# GND_FAULT.net
KiCad netlist of a schematic drawn in Altium Designer
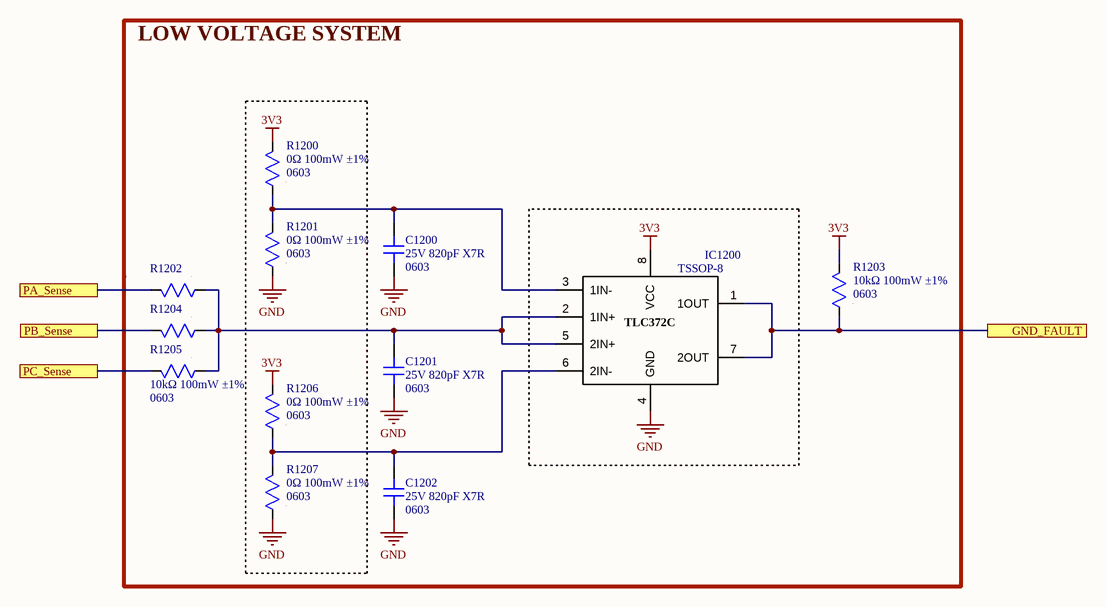
[diagram p0: GND_FAULT.SchDoc]

(export (version "E")
  (design (tool "Eeschema 10.0.6"))
  (components
    (comp (ref "C1200")
      (value "25V 820pF X7R")
      (footprint "CAP SMD 0603")
      (description "Condensadores de cerámica multicapa (MLCC- SMD/SMT) 25V 820pF X7R 0603 1 0% Tol")
      (fields
        (field (name "PACKAGE") "0603")
        (field (name "MPN") "06033C821KAT2A")
        (field (name "MANUFACTURER") "KYOCERA AVX")
      )
      (libsource (lib "eUSR_Database") (part "CAP non polarized"))
    )
    (comp (ref "C1201")
      (value "25V 820pF X7R")
      (footprint "CAP SMD 0603")
      (description "Condensadores de cerámica multicapa (MLCC- SMD/SMT) 25V 820pF X7R 0603 1 0% Tol")
      (fields
        (field (name "PACKAGE") "0603")
        (field (name "MPN") "06033C821KAT2A")
        (field (name "MANUFACTURER") "KYOCERA AVX")
      )
      (libsource (lib "eUSR_Database") (part "CAP non polarized"))
    )
    (comp (ref "C1202")
      (value "25V 820pF X7R")
      (footprint "CAP SMD 0603")
      (description "Condensadores de cerámica multicapa (MLCC- SMD/SMT) 25V 820pF X7R 0603 1 0% Tol")
      (fields
        (field (name "PACKAGE") "0603")
        (field (name "MPN") "06033C821KAT2A")
        (field (name "MANUFACTURER") "KYOCERA AVX")
      )
      (libsource (lib "eUSR_Database") (part "CAP non polarized"))
    )
    (comp (ref "IC1200")
      (value "TLC372C")
      (footprint "TSSOP-8")
      (description "Comparadores analógicos Dual Differential A 595-TLC372CPW A 595- A 595-TLC372CPW")
      (fields
        (field (name "PACKAGE") "TSSOP-8")
        (field (name "MPN") "TLC372CPWR")
        (field (name "MANUFACTURER") "Texas Instruments")
      )
      (libsource (lib "eUSR_Database") (part "TLC372C"))
    )
    (comp (ref "R1200")
      (value "0Ω 100mW ±1%")
      (footprint "RES SMD 0603")
      (description "Resistores de película gruesa - SMD WRIS-RSKS <0.05 Ohms 0.1 W Jumper 0603 AEC-Q200")
      (fields
        (field (name "PACKAGE") "0603")
        (field (name "MPN") "560112116001")
        (field (name "MANUFACTURER") "Wurth Elektronik")
      )
      (libsource (lib "eUSR_Database") (part "RES"))
    )
    (comp (ref "R1201")
      (value "0Ω 100mW ±1%")
      (footprint "RES SMD 0603")
      (description "Resistores de película gruesa - SMD WRIS-RSKS <0.05 Ohms 0.1 W Jumper 0603 AEC-Q200")
      (fields
        (field (name "PACKAGE") "0603")
        (field (name "MPN") "560112116001")
        (field (name "MANUFACTURER") "Wurth Elektronik")
      )
      (libsource (lib "eUSR_Database") (part "RES"))
    )
    (comp (ref "R1202")
      (value "RES")
      (footprint "RES SMD 0603")
      (description "Resistores de película gruesa - SMD WRIS-RSKS 10 kOhms 1 % 0.1 W 0603 AEC-Q200")
      (fields (field (name "MPN") "560112116005") (field (name "MANUFACTURER") "Wurth Elektronik"))
      (libsource (lib "eUSR_Database") (part "RES"))
    )
    (comp (ref "R1203")
      (value "10kΩ 100mW ±1%")
      (footprint "RES SMD 0603")
      (description "Resistores de película gruesa - SMD WRIS-RSKS 10 kOhms 1 % 0.1 W 0603 AEC-Q200")
      (fields
        (field (name "PACKAGE") "0603")
        (field (name "MPN") "560112116005")
        (field (name "MANUFACTURER") "Wurth Elektronik")
      )
      (libsource (lib "eUSR_Database") (part "RES"))
    )
    (comp (ref "R1204")
      (value "RES")
      (footprint "RES SMD 0603")
      (description "Resistores de película gruesa - SMD WRIS-RSKS 10 kOhms 1 % 0.1 W 0603 AEC-Q200")
      (fields (field (name "MPN") "560112116005") (field (name "MANUFACTURER") "Wurth Elektronik"))
      (libsource (lib "eUSR_Database") (part "RES"))
    )
    (comp (ref "R1205")
      (value "10kΩ 100mW ±1%")
      (footprint "RES SMD 0603")
      (description "Resistores de película gruesa - SMD WRIS-RSKS 10 kOhms 1 % 0.1 W 0603 AEC-Q200")
      (fields
        (field (name "PACKAGE") "0603")
        (field (name "MPN") "560112116005")
        (field (name "MANUFACTURER") "Wurth Elektronik")
      )
      (libsource (lib "eUSR_Database") (part "RES"))
    )
    (comp (ref "R1206")
      (value "0Ω 100mW ±1%")
      (footprint "RES SMD 0603")
      (description "Resistores de película gruesa - SMD WRIS-RSKS <0.05 Ohms 0.1 W Jumper 0603 AEC-Q200")
      (fields
        (field (name "PACKAGE") "0603")
        (field (name "MPN") "560112116001")
        (field (name "MANUFACTURER") "Wurth Elektronik")
      )
      (libsource (lib "eUSR_Database") (part "RES"))
    )
    (comp (ref "R1207")
      (value "0Ω 100mW ±1%")
      (footprint "RES SMD 0603")
      (description "Resistores de película gruesa - SMD WRIS-RSKS <0.05 Ohms 0.1 W Jumper 0603 AEC-Q200")
      (fields
        (field (name "PACKAGE") "0603")
        (field (name "MPN") "560112116001")
        (field (name "MANUFACTURER") "Wurth Elektronik")
      )
      (libsource (lib "eUSR_Database") (part "RES"))
    )
  )
  (nets
    (net (code "1") (name "/GND_FAULT") (class "Default")
      (node (ref "IC1200") (pin "1") (pinfunction "1OUT_1") (pintype "passive"))
      (node (ref "IC1200") (pin "7") (pinfunction "2OUT_7") (pintype "passive"))
      (node (ref "R1203") (pin "1") (pinfunction "1_1") (pintype "passive"))
    )
    (net (code "2") (name "/PA_Sense") (class "Default")
      (node (ref "R1202") (pin "2") (pinfunction "2_2") (pintype "passive"))
    )
    (net (code "3") (name "/PB_Sense") (class "Default")
      (node (ref "R1204") (pin "2") (pinfunction "2_2") (pintype "passive"))
    )
    (net (code "4") (name "/PC_Sense") (class "Default")
      (node (ref "R1205") (pin "2") (pinfunction "2_2") (pintype "passive"))
    )
    (net (code "5") (name "3V3") (class "Default")
      (node (ref "IC1200") (pin "8") (pinfunction "VCC_8") (pintype "passive"))
      (node (ref "R1200") (pin "2") (pinfunction "2_2") (pintype "passive"))
      (node (ref "R1203") (pin "2") (pinfunction "2_2") (pintype "passive"))
      (node (ref "R1206") (pin "2") (pinfunction "2_2") (pintype "passive"))
    )
    (net (code "6") (name "GND") (class "Default")
      (node (ref "C1200") (pin "2") (pinfunction "2_2") (pintype "passive"))
      (node (ref "C1201") (pin "2") (pinfunction "2_2") (pintype "passive"))
      (node (ref "C1202") (pin "2") (pinfunction "2_2") (pintype "passive"))
      (node (ref "IC1200") (pin "4") (pinfunction "GND_4") (pintype "passive"))
      (node (ref "R1201") (pin "1") (pinfunction "1_1") (pintype "passive"))
      (node (ref "R1207") (pin "1") (pinfunction "1_1") (pintype "passive"))
    )
    (net (code "7") (name "Net-(IC1200-1IN+)") (class "Default")
      (node (ref "C1201") (pin "1") (pinfunction "1_1") (pintype "passive"))
      (node (ref "IC1200") (pin "2") (pinfunction "1IN+_2") (pintype "passive"))
      (node (ref "IC1200") (pin "5") (pinfunction "2IN+_5") (pintype "passive"))
      (node (ref "R1202") (pin "1") (pinfunction "1_1") (pintype "passive"))
      (node (ref "R1204") (pin "1") (pinfunction "1_1") (pintype "passive"))
      (node (ref "R1205") (pin "1") (pinfunction "1_1") (pintype "passive"))
    )
    (net (code "8") (name "Net-(IC1200-1IN-)") (class "Default")
      (node (ref "C1200") (pin "1") (pinfunction "1_1") (pintype "passive"))
      (node (ref "IC1200") (pin "3") (pinfunction "1IN-_3") (pintype "passive"))
      (node (ref "R1200") (pin "1") (pinfunction "1_1") (pintype "passive"))
      (node (ref "R1201") (pin "2") (pinfunction "2_2") (pintype "passive"))
    )
    (net (code "9") (name "Net-(IC1200-2IN-)") (class "Default")
      (node (ref "C1202") (pin "1") (pinfunction "1_1") (pintype "passive"))
      (node (ref "IC1200") (pin "6") (pinfunction "2IN-_6") (pintype "passive"))
      (node (ref "R1206") (pin "1") (pinfunction "1_1") (pintype "passive"))
      (node (ref "R1207") (pin "2") (pinfunction "2_2") (pintype "passive"))
    )
  )
)
